# power.net
KiCad netlist of a schematic drawn in Altium Designer
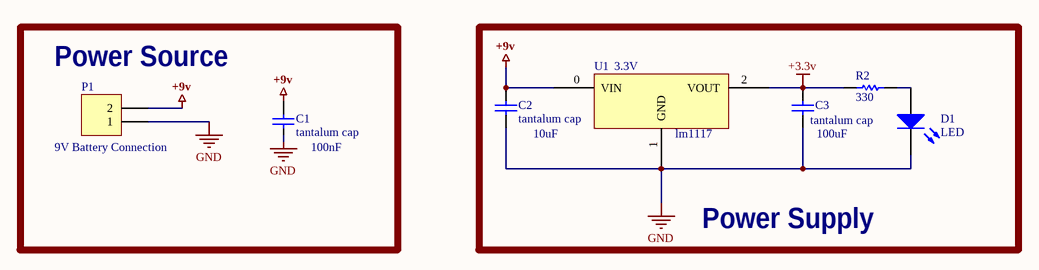
[diagram p0: power.SchDoc]

(export (version "E")
  (design (tool "Eeschema 10.0.6"))
  (components
    (comp (ref "C1")
      (value "tantalum cap")
      (footprint "C1206tancap")
      (description "Capacitor (Semiconductor SIM Model)")
      (fields (field (name "ALTIUM_VALUE") "100nF") (field (name "PUBLISHER") "Altium Limited"))
      (libsource (lib "4. smartmcu") (part "Cap Semi_5"))
    )
    (comp (ref "C2")
      (value "tantalum cap")
      (footprint "C1206tancap")
      (description "Capacitor (Semiconductor SIM Model)")
      (fields (field (name "ALTIUM_VALUE") "10uF") (field (name "PUBLISHER") "Altium Limited"))
      (libsource (lib "4. smartmcu") (part "Cap Semi_5"))
    )
    (comp (ref "C3")
      (value "tantalum cap")
      (footprint "C1206tancap")
      (description "Capacitor (Semiconductor SIM Model)")
      (fields (field (name "ALTIUM_VALUE") "100uF") (field (name "PUBLISHER") "Altium Limited"))
      (libsource (lib "4. smartmcu") (part "Cap Semi_6"))
    )
    (comp (ref "D1")
      (value "LED")
      (footprint "MY_LED_0805")
      (description "Typical INFRARED GaAs LED")
      (fields (field (name "ASID PART NUMBER") "LED-AS"))
      (libsource (lib "1. Mylib Rev 4") (part "LED"))
    )
    (comp (ref "P1")
      (value "9V Battery Connection")
      (footprint "HDR1X2H3dbody")
      (description "Header, 2-Pin, Right Angle")
      (fields (field (name "VOLTAGE") "9V") (field (name "PUBLISHER") "Altium Limited"))
      (libsource (lib "4. smartmcu") (part "Header 2H"))
    )
    (comp (ref "R2")
      (value "330")
      (footprint "MY_0805")
      (description "Standard resistor")
      (fields (field (name "ASID PART NUMBER") "Res-AS"))
      (libsource (lib "1. Mylib Rev 4") (part "Res"))
    )
    (comp (ref "U1")
      (value "lm1117")
      (footprint "4-Pin SOT")
      (fields (field (name "OUTPUT VOLTAG") "3.3V"))
      (libsource (lib "4. smartmcu") (part "lm1117"))
    )
  )
  (nets
    (net (code "1") (name "+3.3v") (class "Default")
      (node (ref "C3") (pin "2") (pinfunction "2_2") (pintype "passive"))
      (node (ref "R2") (pin "1") (pinfunction "1_1") (pintype "passive"))
      (node (ref "U1") (pin "2") (pinfunction "VOUT_2") (pintype "passive"))
    )
    (net (code "2") (name "+9v") (class "Default")
      (node (ref "C1") (pin "2") (pinfunction "2_2") (pintype "passive"))
      (node (ref "C2") (pin "2") (pinfunction "2_2") (pintype "passive"))
      (node (ref "P1") (pin "2") (pinfunction "2_2") (pintype "passive"))
      (node (ref "U1") (pin "0") (pinfunction "VIN_0") (pintype "passive"))
    )
    (net (code "3") (name "GND") (class "Default")
      (node (ref "C1") (pin "1") (pinfunction "1_1") (pintype "passive"))
      (node (ref "C2") (pin "1") (pinfunction "1_1") (pintype "passive"))
      (node (ref "C3") (pin "1") (pinfunction "1_1") (pintype "passive"))
      (node (ref "D1") (pin "K") (pinfunction "K_K") (pintype "passive"))
      (node (ref "P1") (pin "1") (pinfunction "1_1") (pintype "passive"))
      (node (ref "U1") (pin "1") (pinfunction "GND_1") (pintype "passive"))
    )
    (net (code "4") (name "Net-(D1-PadA)") (class "Default")
      (node (ref "D1") (pin "A") (pinfunction "A_A") (pintype "passive"))
      (node (ref "R2") (pin "2") (pinfunction "2_2") (pintype "passive"))
    )
  )
)
